# SINGLE_KEY_MACROcorrectfootprint.net
KiCad netlist of a schematic drawn in EAGLE
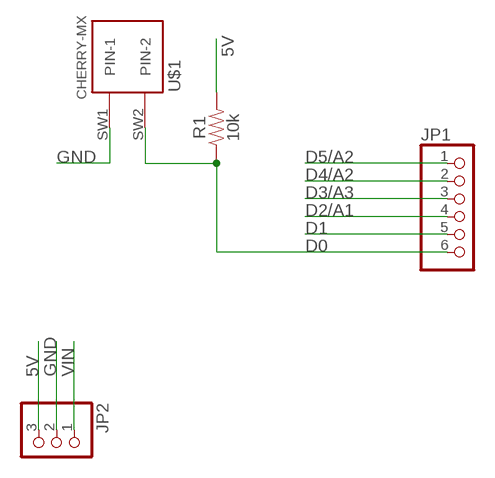
[diagram p0: schematic, sheet 1]

(export (version "E")
  (design (tool "Eeschema 10.0.6"))
  (components
    (comp (ref "JP1")
      (value "PINHD-1X6")
      (footprint "eagle-import:1X06")
      (libsource (lib "eagle-import") (part "PINHD-1X6"))
    )
    (comp (ref "JP2")
      (value "PINHD-1X3")
      (footprint "eagle-import:1X03")
      (libsource (lib "eagle-import") (part "PINHD-1X3"))
    )
    (comp (ref "R1")
      (value "10k")
      (footprint "eagle-import:AXIAL-0.3")
      (libsource (lib "eagle-import") (part "10KOHM-HORIZ-1/4W-1%"))
    )
    (comp (ref "U$1")
      (value "CHERRY-MX")
      (footprint "eagle-import:CHERRY-MX")
      (libsource (lib "eagle-import") (part "CHERRY-MX"))
    )
  )
  (nets
    (net (code "1") (name "/5V") (class "Default")
      (node (ref "JP2") (pin "3") (pinfunction "3_3") (pintype "passive"))
      (node (ref "R1") (pin "P$2") (pinfunction "2_P$2") (pintype "passive"))
    )
    (net (code "2") (name "/D0") (class "Default")
      (node (ref "JP1") (pin "6") (pinfunction "6_6") (pintype "passive"))
      (node (ref "R1") (pin "P$1") (pinfunction "1_P$1") (pintype "passive"))
      (node (ref "U$1") (pin "SW2") (pinfunction "PIN-2_SW2") (pintype "bidirectional"))
    )
    (net (code "3") (name "/D1") (class "Default")
      (node (ref "JP1") (pin "5") (pinfunction "5_5") (pintype "passive"))
    )
    (net (code "4") (name "/D2{slash}A1") (class "Default")
      (node (ref "JP1") (pin "4") (pinfunction "4_4") (pintype "passive"))
    )
    (net (code "5") (name "/D3{slash}A3") (class "Default")
      (node (ref "JP1") (pin "3") (pinfunction "3_3") (pintype "passive"))
    )
    (net (code "6") (name "/D4{slash}A2") (class "Default")
      (node (ref "JP1") (pin "2") (pinfunction "2_2") (pintype "passive"))
    )
    (net (code "7") (name "/D5{slash}A2") (class "Default")
      (node (ref "JP1") (pin "1") (pinfunction "1_1") (pintype "passive"))
    )
    (net (code "8") (name "/GND") (class "Default")
      (node (ref "JP2") (pin "2") (pinfunction "2_2") (pintype "passive"))
      (node (ref "U$1") (pin "SW1") (pinfunction "PIN-1_SW1") (pintype "bidirectional"))
    )
    (net (code "9") (name "/VIN") (class "Default")
      (node (ref "JP2") (pin "1") (pinfunction "1_1") (pintype "passive"))
    )
  )
)
